# usb_conn.net
KiCad netlist of a schematic drawn in Altium Designer
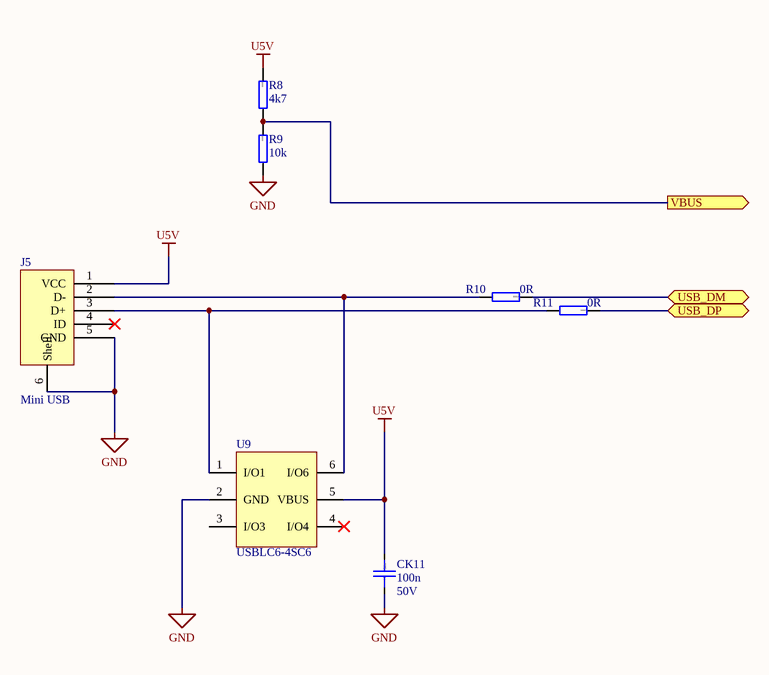
[diagram p0: usb_conn.SchDoc]

(export (version "E")
  (design (tool "Eeschema 10.0.6"))
  (components
    (comp (ref "CK11")
      (value "100n")
      (footprint "CAP0603")
      (description "50V 100nF X7R ±10% 0603 Multilayer Ceramic Capacitors MLCC - SMD/SMT ROHS")
      (fields (field (name "JLCPCB PART") "C14663") (field (name "VOLTAGE RATING") "50V"))
      (libsource (lib "Kubikova ultra knihovna") (part "Cap 100n 0603"))
    )
    (comp (ref "J5")
      (value "Mini USB")
      (footprint "USB B Mini horizontal")
      (description "Konektor: USB B mini; zásuvka; na PCB; SMT; PIN: 5; vodorovné")
      (fields (field (name "TME PART") "MX-67503-1020"))
      (libsource (lib "Kubikova ultra knihovna") (part "Mini USB"))
    )
    (comp (ref "R8")
      (value "4k7")
      (footprint "RESC2012X06N(SMR0805)")
      (description "125mW Thick Film Resistors 150V ±100ppm/℃ ±1% 4.7kΩ 0805 Chip Resistor - Surface Mount ROHS")
      (fields (field (name "JLCPCB PART") "C17673") (field (name "AUTHOR") "JP/27.03.2014"))
      (libsource (lib "Kubikova ultra knihovna") (part "Res 4k7 0805"))
    )
    (comp (ref "R9")
      (value "10k")
      (footprint "RESC2012X06N(SMR0805)")
      (description "125mW Thick Film Resistors 150V ±100ppm/℃ ±1% 10kΩ 0805 Chip Resistor - Surface Mount ROHS")
      (fields (field (name "JLCPCB PART") "C17414"))
      (libsource (lib "Kubikova ultra knihovna") (part "Res 10k 0805"))
    )
    (comp (ref "R10")
      (value "0R")
      (footprint "RESC2012X06N(SMR0805)")
      (description "125mW Thick Film Resistors 150V ±800ppm/℃ ±1% 0Ω 0805 Chip Resistor - Surface Mount ROHS")
      (fields (field (name "JLCPCB PART") "C17477") (field (name "AUTHOR") "JP/27.03.2014"))
      (libsource (lib "Kubikova ultra knihovna") (part "Res 0R 0805"))
    )
    (comp (ref "R11")
      (value "0R")
      (footprint "RESC2012X06N(SMR0805)")
      (description "125mW Thick Film Resistors 150V ±800ppm/℃ ±1% 0Ω 0805 Chip Resistor - Surface Mount ROHS")
      (fields (field (name "JLCPCB PART") "C17477") (field (name "AUTHOR") "JP/27.03.2014"))
      (libsource (lib "Kubikova ultra knihovna") (part "Res 0R 0805"))
    )
    (comp (ref "U9")
      (value "USBLC6-4SC6")
      (footprint "SOT23-6")
      (description "5A 17V 6V Unidirectional 5.25V SOT-23-6 ESD and Surge Protection (TVS/ESD) ROHS")
      (fields (field (name "JLCPCB PART") "C111212"))
      (libsource (lib "Kubikova ultra knihovna") (part "USBLC6-4SC6"))
    )
  )
  (nets
    (net (code "1") (name "/USB_DM") (class "Default")
      (node (ref "R10") (pin "2") (pinfunction "2_2") (pintype "passive"))
    )
    (net (code "2") (name "/USB_DP") (class "Default")
      (node (ref "R11") (pin "2") (pinfunction "2_2") (pintype "passive"))
    )
    (net (code "3") (name "/VBUS") (class "Default")
      (node (ref "R8") (pin "1") (pinfunction "1_1") (pintype "passive"))
      (node (ref "R9") (pin "2") (pinfunction "2_2") (pintype "passive"))
    )
    (net (code "4") (name "GND") (class "Default")
      (node (ref "CK11") (pin "2") (pinfunction "2_2") (pintype "passive"))
      (node (ref "J5") (pin "5") (pinfunction "GND_5") (pintype "passive"))
      (node (ref "J5") (pin "6") (pinfunction "Shell_6") (pintype "passive"))
      (node (ref "R9") (pin "1") (pinfunction "1_1") (pintype "passive"))
      (node (ref "U9") (pin "2") (pinfunction "GND_2") (pintype "passive"))
    )
    (net (code "5") (name "Net-(J5-D+)") (class "Default")
      (node (ref "J5") (pin "3") (pinfunction "D+_3") (pintype "passive"))
      (node (ref "R11") (pin "1") (pinfunction "1_1") (pintype "passive"))
      (node (ref "U9") (pin "1") (pinfunction "I/O1_1") (pintype "passive"))
    )
    (net (code "6") (name "Net-(J5-D-)") (class "Default")
      (node (ref "J5") (pin "2") (pinfunction "D-_2") (pintype "passive"))
      (node (ref "R10") (pin "1") (pinfunction "1_1") (pintype "passive"))
      (node (ref "U9") (pin "6") (pinfunction "I/O6_6") (pintype "passive"))
    )
    (net (code "7") (name "U5V") (class "Default")
      (node (ref "CK11") (pin "1") (pinfunction "1_1") (pintype "passive"))
      (node (ref "J5") (pin "1") (pinfunction "VCC_1") (pintype "passive"))
      (node (ref "R8") (pin "2") (pinfunction "2_2") (pintype "passive"))
      (node (ref "U9") (pin "5") (pinfunction "VBUS_5") (pintype "passive"))
    )
    (net (code "8") (name "unconnected-(J5-ID-Pad4)") (class "Default")
      (node (ref "J5") (pin "4") (pinfunction "ID_4") (pintype "passive+no_connect"))
    )
    (net (code "9") (name "unconnected-(U9-I{slash}O3-Pad3)") (class "Default")
      (node (ref "U9") (pin "3") (pinfunction "I/O3_3") (pintype "passive"))
    )
    (net (code "10") (name "unconnected-(U9-I{slash}O4-Pad4)") (class "Default")
      (node (ref "U9") (pin "4") (pinfunction "I/O4_4") (pintype "passive+no_connect"))
    )
  )
)
